# PICKIT4-adaptor.net
KiCad netlist of a schematic drawn in EAGLE
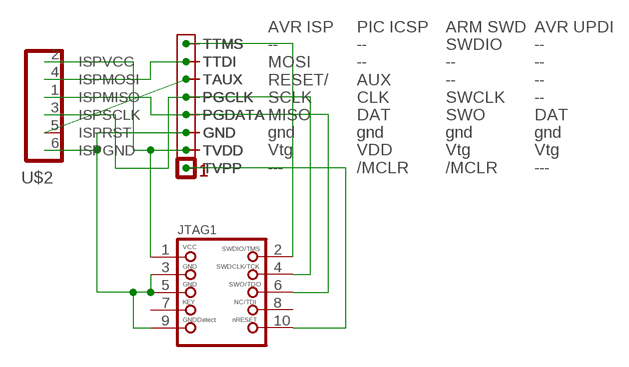
[diagram p0: schematic, sheet 1]

(export (version "E")
  (design (tool "Eeschema 10.0.6"))
  (components
    (comp (ref "JTAG1")
      (value "JTAG-CORTEXM3")
      (footprint "eagle-import:2X05_1.27MM_SMT")
      (libsource (lib "eagle-import") (part "JTAG-CORTEXM3"))
    )
    (comp (ref "U$1")
      (value "PICKIT4PINHDR")
      (footprint "eagle-import:PINHEAD1X8")
      (libsource (lib "eagle-import") (part "PICKIT4PINHDR"))
    )
    (comp (ref "U$2")
      (value "AVR-ISP")
      (footprint "eagle-import:6PINS")
      (libsource (lib "eagle-import") (part "AVR-ISP"))
    )
    (comp (ref "U$3")
      (value "PICKIT4PINHDR")
      (footprint "eagle-import:PINHEAD1X8")
      (libsource (lib "eagle-import") (part "PICKIT4PINHDR"))
    )
    (comp (ref "U$4")
      (value "PICKIT4PINHDR")
      (footprint "eagle-import:PINHEAD1X8")
      (libsource (lib "eagle-import") (part "PICKIT4PINHDR"))
    )
  )
  (nets
    (net (code "1") (name "Net-(U$1A-GND)") (class "Default")
      (node (ref "JTAG1") (pin "3") (pinfunction "3_3") (pintype "passive"))
      (node (ref "JTAG1") (pin "5") (pinfunction "5_5") (pintype "passive"))
      (node (ref "JTAG1") (pin "9") (pinfunction "9_9") (pintype "passive"))
      (node (ref "U$1") (pin "P$3") (pinfunction "GND_P$3") (pintype "power_in"))
      (node (ref "U$2") (pin "6") (pinfunction "ISPGND_6") (pintype "power_in"))
      (node (ref "U$3") (pin "P$3") (pinfunction "GND_P$3") (pintype "power_in"))
      (node (ref "U$4") (pin "P$3") (pinfunction "GND_P$3") (pintype "power_in"))
    )
    (net (code "2") (name "Net-(U$1A-PGCLK)") (class "Default")
      (node (ref "JTAG1") (pin "4") (pinfunction "4_4") (pintype "passive"))
      (node (ref "U$1") (pin "P$5") (pinfunction "PGCLK_P$5") (pintype "bidirectional"))
      (node (ref "U$2") (pin "3") (pinfunction "ISPSCLK_3") (pintype "output"))
      (node (ref "U$3") (pin "P$5") (pinfunction "PGCLK_P$5") (pintype "bidirectional"))
      (node (ref "U$4") (pin "P$5") (pinfunction "PGCLK_P$5") (pintype "bidirectional"))
    )
    (net (code "3") (name "Net-(U$1A-PGDATA)") (class "Default")
      (node (ref "JTAG1") (pin "6") (pinfunction "6_6") (pintype "passive"))
      (node (ref "U$1") (pin "P$4") (pinfunction "PGDATA_P$4") (pintype "bidirectional"))
      (node (ref "U$2") (pin "1") (pinfunction "ISPMISO_1") (pintype "input"))
      (node (ref "U$3") (pin "P$4") (pinfunction "PGDATA_P$4") (pintype "bidirectional"))
      (node (ref "U$4") (pin "P$4") (pinfunction "PGDATA_P$4") (pintype "bidirectional"))
    )
    (net (code "4") (name "Net-(U$1A-TAUX)") (class "Default")
      (node (ref "U$1") (pin "P$6") (pinfunction "TAUX_P$6") (pintype "bidirectional"))
      (node (ref "U$2") (pin "5") (pinfunction "ISPRST_5") (pintype "input"))
      (node (ref "U$3") (pin "P$6") (pinfunction "TAUX_P$6") (pintype "bidirectional"))
      (node (ref "U$4") (pin "P$6") (pinfunction "TAUX_P$6") (pintype "bidirectional"))
    )
    (net (code "5") (name "Net-(U$1A-TTDI)") (class "Default")
      (node (ref "U$1") (pin "P$7") (pinfunction "TTDI_P$7") (pintype "bidirectional"))
      (node (ref "U$2") (pin "4") (pinfunction "ISPMOSI_4") (pintype "output"))
      (node (ref "U$3") (pin "P$7") (pinfunction "TTDI_P$7") (pintype "bidirectional"))
      (node (ref "U$4") (pin "P$7") (pinfunction "TTDI_P$7") (pintype "bidirectional"))
    )
    (net (code "6") (name "Net-(U$1A-TTMS)") (class "Default")
      (node (ref "JTAG1") (pin "2") (pinfunction "2_2") (pintype "passive"))
      (node (ref "U$1") (pin "P$8") (pinfunction "TTMS_P$8") (pintype "bidirectional"))
      (node (ref "U$3") (pin "P$8") (pinfunction "TTMS_P$8") (pintype "bidirectional"))
      (node (ref "U$4") (pin "P$8") (pinfunction "TTMS_P$8") (pintype "bidirectional"))
    )
    (net (code "7") (name "Net-(U$1A-TVDD)") (class "Default")
      (node (ref "JTAG1") (pin "1") (pinfunction "1_1") (pintype "passive"))
      (node (ref "U$1") (pin "P$2") (pinfunction "TVDD_P$2") (pintype "bidirectional"))
      (node (ref "U$2") (pin "2") (pinfunction "ISPVCC_2") (pintype "power_in"))
      (node (ref "U$3") (pin "P$2") (pinfunction "TVDD_P$2") (pintype "bidirectional"))
      (node (ref "U$4") (pin "P$2") (pinfunction "TVDD_P$2") (pintype "bidirectional"))
    )
    (net (code "8") (name "Net-(U$1A-TVPP)") (class "Default")
      (node (ref "JTAG1") (pin "10") (pinfunction "10_10") (pintype "passive"))
      (node (ref "U$1") (pin "P$1") (pinfunction "TVPP_P$1") (pintype "bidirectional"))
      (node (ref "U$3") (pin "P$1") (pinfunction "TVPP_P$1") (pintype "bidirectional"))
      (node (ref "U$4") (pin "P$1") (pinfunction "TVPP_P$1") (pintype "bidirectional"))
    )
    (net (code "9") (name "unconnected-(JTAG1-Pad7)") (class "Default")
      (node (ref "JTAG1") (pin "7") (pinfunction "7_7") (pintype "passive"))
    )
    (net (code "10") (name "unconnected-(JTAG1-Pad8)") (class "Default")
      (node (ref "JTAG1") (pin "8") (pinfunction "8_8") (pintype "passive"))
    )
  )
)
